# Sheet1.net
KiCad netlist of a schematic drawn in Altium Designer
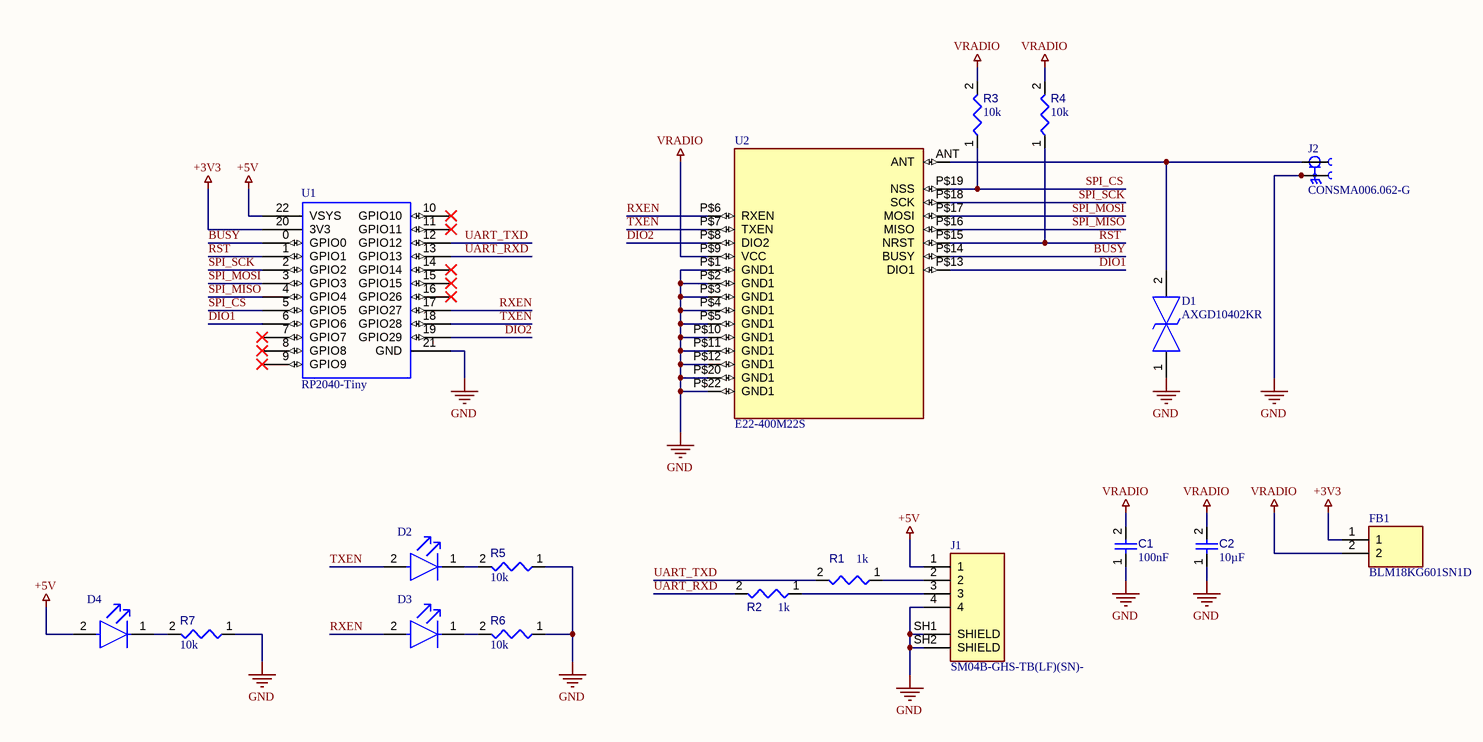
[diagram p0: Sheet1.SchDoc]

(export (version "E")
  (design (tool "Eeschema 10.0.6"))
  (components
    (comp (ref "C1")
      (value "100nF")
      (footprint "CAPC0402(1005)60_L")
      (description "Chip Capacitor, 100nF +/-20%, 10V, 0402, Thickness 0.6 mm")
      (fields (field (name "TOLERANCE") "20%") (field (name "Comment") "Capacitor 100nF +/-20% 10V 0402"))
      (libsource (lib "PWr in Space team") (part "CAP-NP-2"))
    )
    (comp (ref "C2")
      (value "10µF")
      (footprint "CAPC0603(1608)100_L")
      (description "Chip Capacitor, 10µF +/-20%, 10V, 0603, Thickness 1 mm")
      (fields (field (name "TOLERANCE") "10%") (field (name "Comment") "Capacitor 10µF +/-20% 10V 0603"))
      (libsource (lib "PWr in Space team") (part "CAP-NP-2"))
    )
    (comp (ref "D1")
      (value "AXGD10402KR")
      (footprint "SamacSys:DIONM105X51N")
      (description "TVS Diode (Bi-directional)")
      (fields (field (name "MOUSER PART NUMBER") "576-AXGD10402KR"))
      (libsource (lib "*") (part "AXGD10402KR"))
    )
    (comp (ref "D2")
      (value "~")
      (footprint "FP-LTST-C191TBKT-MFG")
      (description "LED BLUE CLEAR CHIP SMD")
      (libsource (lib "Altium Content Vault") (part "8706943c75ba83719d021d2fdc84c58"))
    )
    (comp (ref "D3")
      (value "~")
      (footprint "FP-LTST-C191TBKT-MFG")
      (description "LED BLUE CLEAR CHIP SMD")
      (libsource (lib "Altium Content Vault") (part "8706943c75ba83719d021d2fdc84c58"))
    )
    (comp (ref "D4")
      (value "~")
      (footprint "FP-LTST-C191TBKT-MFG")
      (description "LED BLUE CLEAR CHIP SMD")
      (libsource (lib "Altium Content Vault") (part "8706943c75ba83719d021d2fdc84c58"))
    )
    (comp (ref "FB1")
      (value "BLM18KG601SN1D")
      (footprint "SamacSys:BLM18EG121SH1D")
      (description "Ferrite Bead")
      (fields (field (name "MOUSER PART NUMBER") "81-BLM18KG601SN1D"))
      (libsource (lib "*") (part "BLM18KG601SN1D"))
    )
    (comp (ref "J1")
      (value "SM04B-GHS-TB(LF)(SN)-")
      (footprint "SM04B-GHS-TB(LF)(SN)-:JST_SM04B-GHS-TB(LF)(SN)-")
      (description "Conn Header Gh Side 4pos 1.25mm")
      (fields (field (name "MF") "{'manufacturer': u'JST Sales'}"))
      (libsource (lib "SM04B-GHS-TB(LF)(SN)-") (part "SM04B-GHS-TB(LF)(SN)-"))
    )
    (comp (ref "J2")
      (value "CONSMA006.062-G")
      (footprint "LINX_CONSMA006.062-G")
      (description "SMA FEMALE EDGE MULTI-MOUNT FOR 0.062\" THICK BOARD")
      (fields (field (name "MF") "{'manufacturer': u'TE Connectivity / Linx Technologies'}"))
      (libsource (lib "SnapEDA_Library") (part "CONSMA006.062-G"))
    )
    (comp (ref "R1")
      (value "1k")
      (footprint "RESC0402(1005)_L")
      (description "Chip Resistor, 1 kOhms, +/-5 %, 63 mW, -55 to 155 degC, 0402")
      (fields (field (name "TOLERANCE") "5%") (field (name "POWER") "63mW"))
      (libsource (lib "PWr in Space team") (part "RES-2"))
    )
    (comp (ref "R2")
      (value "1k")
      (footprint "RESC0402(1005)_L")
      (description "Chip Resistor, 1 kOhms, +/-5 %, 63 mW, -55 to 155 degC, 0402")
      (fields (field (name "TOLERANCE") "5%") (field (name "POWER") "63mW"))
      (libsource (lib "PWr in Space team") (part "RES-2"))
    )
    (comp (ref "R3")
      (value "10k")
      (footprint "RESC0402(1005)_L")
      (description "Chip Resistor, 10 kOhms, +/-1 %, 63 mW, -55 to 125 degC, 0402")
      (fields (field (name "POWER") "63mW") (field (name "TOLERANCE") "1%"))
      (libsource (lib "PWr in Space team") (part "RES-2"))
    )
    (comp (ref "R4")
      (value "10k")
      (footprint "RESC0402(1005)_L")
      (description "Chip Resistor, 10 kOhms, +/-1 %, 63 mW, -55 to 125 degC, 0402")
      (fields (field (name "POWER") "63mW") (field (name "TOLERANCE") "1%"))
      (libsource (lib "PWr in Space team") (part "RES-2"))
    )
    (comp (ref "R5")
      (value "10k")
      (footprint "RESC0402(1005)_L")
      (description "Chip Resistor, 10 kOhms, +/-1 %, 63 mW, -55 to 125 degC, 0402")
      (fields (field (name "POWER") "63mW") (field (name "TOLERANCE") "1%"))
      (libsource (lib "PWr in Space team") (part "RES-2"))
    )
    (comp (ref "R6")
      (value "10k")
      (footprint "RESC0402(1005)_L")
      (description "Chip Resistor, 10 kOhms, +/-1 %, 63 mW, -55 to 125 degC, 0402")
      (fields (field (name "POWER") "63mW") (field (name "TOLERANCE") "1%"))
      (libsource (lib "PWr in Space team") (part "RES-2"))
    )
    (comp (ref "R7")
      (value "10k")
      (footprint "RESC0402(1005)_L")
      (description "Chip Resistor, 10 kOhms, +/-1 %, 63 mW, -55 to 125 degC, 0402")
      (fields (field (name "POWER") "63mW") (field (name "TOLERANCE") "1%"))
      (libsource (lib "PWr in Space team") (part "RES-2"))
    )
    (comp (ref "U1")
      (value "RP2040-Tiny")
      (footprint "RP2040-Tiny-Footprint-1")
      (libsource (lib "PWr in Space team") (part "RP2040-Tiny-Symbol-1"))
    )
    (comp (ref "U2")
      (value "E22-400M22S")
      (footprint "E22-900M22S")
      (description "SX1262 868/915MHz SPI SMD LoRa Module")
      (fields (field (name "MF") "EBYTE") (field (name "MP") "E22-900M22S"))
      (libsource (lib "PWr in Space team") (part "E22-900M22S"))
    )
  )
  (nets
    (net (code "1") (name "+3V3") (class "Default")
      (node (ref "FB1") (pin "1") (pinfunction "1_1") (pintype "passive"))
      (node (ref "U1") (pin "20") (pinfunction "3V3_20") (pintype "power_in"))
    )
    (net (code "2") (name "+5V") (class "Default")
      (node (ref "D4") (pin "2") (pinfunction "A_2") (pintype "passive"))
      (node (ref "J1") (pin "1") (pinfunction "1_1") (pintype "passive"))
      (node (ref "U1") (pin "22") (pinfunction "VSYS_22") (pintype "power_in"))
    )
    (net (code "3") (name "/BUSY") (class "Default")
      (node (ref "U1") (pin "0") (pinfunction "GPIO0_0") (pintype "bidirectional"))
      (node (ref "U2") (pin "P$14") (pinfunction "BUSY_P$14") (pintype "bidirectional"))
    )
    (net (code "4") (name "/DIO1") (class "Default")
      (node (ref "U1") (pin "6") (pinfunction "GPIO6_6") (pintype "bidirectional"))
      (node (ref "U2") (pin "P$13") (pinfunction "DIO1_P$13") (pintype "bidirectional"))
    )
    (net (code "5") (name "/DIO2") (class "Default")
      (node (ref "U1") (pin "19") (pinfunction "GPIO29_19") (pintype "bidirectional"))
      (node (ref "U2") (pin "P$8") (pinfunction "DIO2_P$8") (pintype "bidirectional"))
    )
    (net (code "6") (name "/RST") (class "Default")
      (node (ref "R4") (pin "1") (pinfunction "1_1") (pintype "passive"))
      (node (ref "U1") (pin "1") (pinfunction "GPIO1_1") (pintype "bidirectional"))
      (node (ref "U2") (pin "P$15") (pinfunction "NRST_P$15") (pintype "bidirectional"))
    )
    (net (code "7") (name "/RXEN") (class "Default")
      (node (ref "D3") (pin "2") (pinfunction "A_2") (pintype "passive"))
      (node (ref "U1") (pin "17") (pinfunction "GPIO27_17") (pintype "bidirectional"))
      (node (ref "U2") (pin "P$6") (pinfunction "RXEN_P$6") (pintype "bidirectional"))
    )
    (net (code "8") (name "/SPI_CS") (class "Default")
      (node (ref "R3") (pin "1") (pinfunction "1_1") (pintype "passive"))
      (node (ref "U1") (pin "5") (pinfunction "GPIO5_5") (pintype "bidirectional"))
      (node (ref "U2") (pin "P$19") (pinfunction "NSS_P$19") (pintype "bidirectional"))
    )
    (net (code "9") (name "/SPI_MISO") (class "Default")
      (node (ref "U1") (pin "4") (pinfunction "GPIO4_4") (pintype "bidirectional"))
      (node (ref "U2") (pin "P$16") (pinfunction "MISO_P$16") (pintype "bidirectional"))
    )
    (net (code "10") (name "/SPI_MOSI") (class "Default")
      (node (ref "U1") (pin "3") (pinfunction "GPIO3_3") (pintype "bidirectional"))
      (node (ref "U2") (pin "P$17") (pinfunction "MOSI_P$17") (pintype "bidirectional"))
    )
    (net (code "11") (name "/SPI_SCK") (class "Default")
      (node (ref "U1") (pin "2") (pinfunction "GPIO2_2") (pintype "bidirectional"))
      (node (ref "U2") (pin "P$18") (pinfunction "SCK_P$18") (pintype "bidirectional"))
    )
    (net (code "12") (name "/TXEN") (class "Default")
      (node (ref "D2") (pin "2") (pinfunction "A_2") (pintype "passive"))
      (node (ref "U1") (pin "18") (pinfunction "GPIO28_18") (pintype "bidirectional"))
      (node (ref "U2") (pin "P$7") (pinfunction "TXEN_P$7") (pintype "bidirectional"))
    )
    (net (code "13") (name "/UART_RXD") (class "Default")
      (node (ref "R2") (pin "2") (pinfunction "2_2") (pintype "passive"))
      (node (ref "U1") (pin "13") (pinfunction "GPIO13_13") (pintype "bidirectional"))
    )
    (net (code "14") (name "/UART_TXD") (class "Default")
      (node (ref "R1") (pin "2") (pinfunction "2_2") (pintype "passive"))
      (node (ref "U1") (pin "12") (pinfunction "GPIO12_12") (pintype "bidirectional"))
    )
    (net (code "15") (name "GND") (class "Default")
      (node (ref "C1") (pin "1") (pinfunction "1_1") (pintype "passive"))
      (node (ref "C2") (pin "1") (pinfunction "1_1") (pintype "passive"))
      (node (ref "D1") (pin "1") (pinfunction "1_1") (pintype "passive"))
      (node (ref "J1") (pin "4") (pinfunction "4_4") (pintype "passive"))
      (node (ref "J1") (pin "SH1") (pinfunction "SHIELD_SH1") (pintype "power_in"))
      (node (ref "J1") (pin "SH2") (pinfunction "SHIELD_SH2") (pintype "power_in"))
      (node (ref "J2") (pin "S1") (pinfunction "2_S1") (pintype "passive"))
      (node (ref "J2") (pin "S2") (pinfunction "2_S2") (pintype "passive"))
      (node (ref "J2") (pin "S3") (pinfunction "2_S3") (pintype "passive"))
      (node (ref "J2") (pin "S4") (pinfunction "2_S4") (pintype "passive"))
      (node (ref "R5") (pin "1") (pinfunction "1_1") (pintype "passive"))
      (node (ref "R6") (pin "1") (pinfunction "1_1") (pintype "passive"))
      (node (ref "R7") (pin "1") (pinfunction "1_1") (pintype "passive"))
      (node (ref "U1") (pin "21") (pinfunction "GND_21") (pintype "power_in"))
      (node (ref "U2") (pin "P$1") (pinfunction "GND1_P$1") (pintype "bidirectional"))
      (node (ref "U2") (pin "P$10") (pinfunction "GND1_P$10") (pintype "bidirectional"))
      (node (ref "U2") (pin "P$11") (pinfunction "GND1_P$11") (pintype "bidirectional"))
      (node (ref "U2") (pin "P$12") (pinfunction "GND1_P$12") (pintype "bidirectional"))
      (node (ref "U2") (pin "P$2") (pinfunction "GND1_P$2") (pintype "bidirectional"))
      (node (ref "U2") (pin "P$20") (pinfunction "GND1_P$20") (pintype "bidirectional"))
      (node (ref "U2") (pin "P$22") (pinfunction "GND1_P$22") (pintype "bidirectional"))
      (node (ref "U2") (pin "P$3") (pinfunction "GND1_P$3") (pintype "bidirectional"))
      (node (ref "U2") (pin "P$4") (pinfunction "GND1_P$4") (pintype "bidirectional"))
      (node (ref "U2") (pin "P$5") (pinfunction "GND1_P$5") (pintype "bidirectional"))
    )
    (net (code "16") (name "Net-(D1-Pad2)") (class "Default")
      (node (ref "D1") (pin "2") (pinfunction "2_2") (pintype "passive"))
      (node (ref "J2") (pin "1") (pinfunction "1_1") (pintype "passive"))
      (node (ref "U2") (pin "ANT") (pinfunction "ANT_ANT") (pintype "bidirectional"))
    )
    (net (code "17") (name "Net-(D2-C)") (class "Default")
      (node (ref "D2") (pin "1") (pinfunction "C_1") (pintype "passive"))
      (node (ref "R5") (pin "2") (pinfunction "2_2") (pintype "passive"))
    )
    (net (code "18") (name "Net-(D3-C)") (class "Default")
      (node (ref "D3") (pin "1") (pinfunction "C_1") (pintype "passive"))
      (node (ref "R6") (pin "2") (pinfunction "2_2") (pintype "passive"))
    )
    (net (code "19") (name "Net-(D4-C)") (class "Default")
      (node (ref "D4") (pin "1") (pinfunction "C_1") (pintype "passive"))
      (node (ref "R7") (pin "2") (pinfunction "2_2") (pintype "passive"))
    )
    (net (code "20") (name "Net-(J1-Pad2)") (class "Default")
      (node (ref "J1") (pin "2") (pinfunction "2_2") (pintype "passive"))
      (node (ref "R1") (pin "1") (pinfunction "1_1") (pintype "passive"))
    )
    (net (code "21") (name "Net-(J1-Pad3)") (class "Default")
      (node (ref "J1") (pin "3") (pinfunction "3_3") (pintype "passive"))
      (node (ref "R2") (pin "1") (pinfunction "1_1") (pintype "passive"))
    )
    (net (code "22") (name "VRADIO") (class "Default")
      (node (ref "C1") (pin "2") (pinfunction "2_2") (pintype "passive"))
      (node (ref "C2") (pin "2") (pinfunction "2_2") (pintype "passive"))
      (node (ref "FB1") (pin "2") (pinfunction "2_2") (pintype "passive"))
      (node (ref "R3") (pin "2") (pinfunction "2_2") (pintype "passive"))
      (node (ref "R4") (pin "2") (pinfunction "2_2") (pintype "passive"))
      (node (ref "U2") (pin "P$9") (pinfunction "VCC_P$9") (pintype "bidirectional"))
    )
    (net (code "23") (name "unconnected-(U1-GPIO7-Pad7)") (class "Default")
      (node (ref "U1") (pin "7") (pinfunction "GPIO7_7") (pintype "bidirectional+no_connect"))
    )
    (net (code "24") (name "unconnected-(U1-GPIO8-Pad8)") (class "Default")
      (node (ref "U1") (pin "8") (pinfunction "GPIO8_8") (pintype "bidirectional+no_connect"))
    )
    (net (code "25") (name "unconnected-(U1-GPIO9-Pad9)") (class "Default")
      (node (ref "U1") (pin "9") (pinfunction "GPIO9_9") (pintype "bidirectional+no_connect"))
    )
    (net (code "26") (name "unconnected-(U1-GPIO10-Pad10)") (class "Default")
      (node (ref "U1") (pin "10") (pinfunction "GPIO10_10") (pintype "bidirectional+no_connect"))
    )
    (net (code "27") (name "unconnected-(U1-GPIO11-Pad11)") (class "Default")
      (node (ref "U1") (pin "11") (pinfunction "GPIO11_11") (pintype "bidirectional+no_connect"))
    )
    (net (code "28") (name "unconnected-(U1-GPIO14-Pad14)") (class "Default")
      (node (ref "U1") (pin "14") (pinfunction "GPIO14_14") (pintype "bidirectional+no_connect"))
    )
    (net (code "29") (name "unconnected-(U1-GPIO15-Pad15)") (class "Default")
      (node (ref "U1") (pin "15") (pinfunction "GPIO15_15") (pintype "bidirectional+no_connect"))
    )
    (net (code "30") (name "unconnected-(U1-GPIO26-Pad16)") (class "Default")
      (node (ref "U1") (pin "16") (pinfunction "GPIO26_16") (pintype "bidirectional+no_connect"))
    )
  )
)
